# 411V2.net
KiCad netlist of a schematic drawn in EAGLE
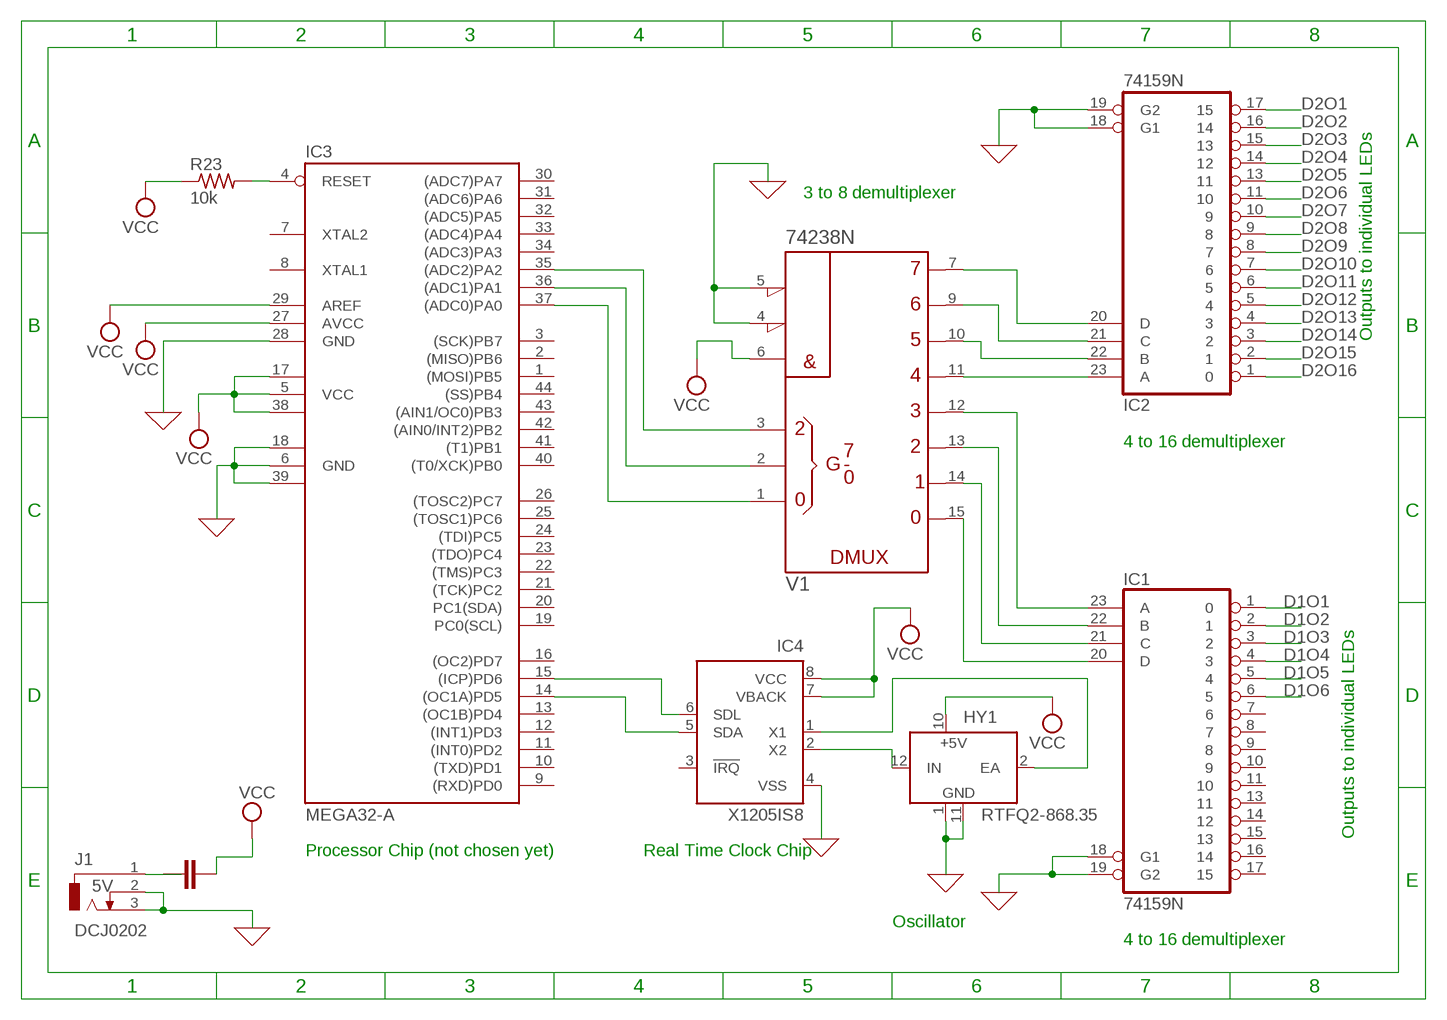
[diagram p0: schematic, sheet 1]
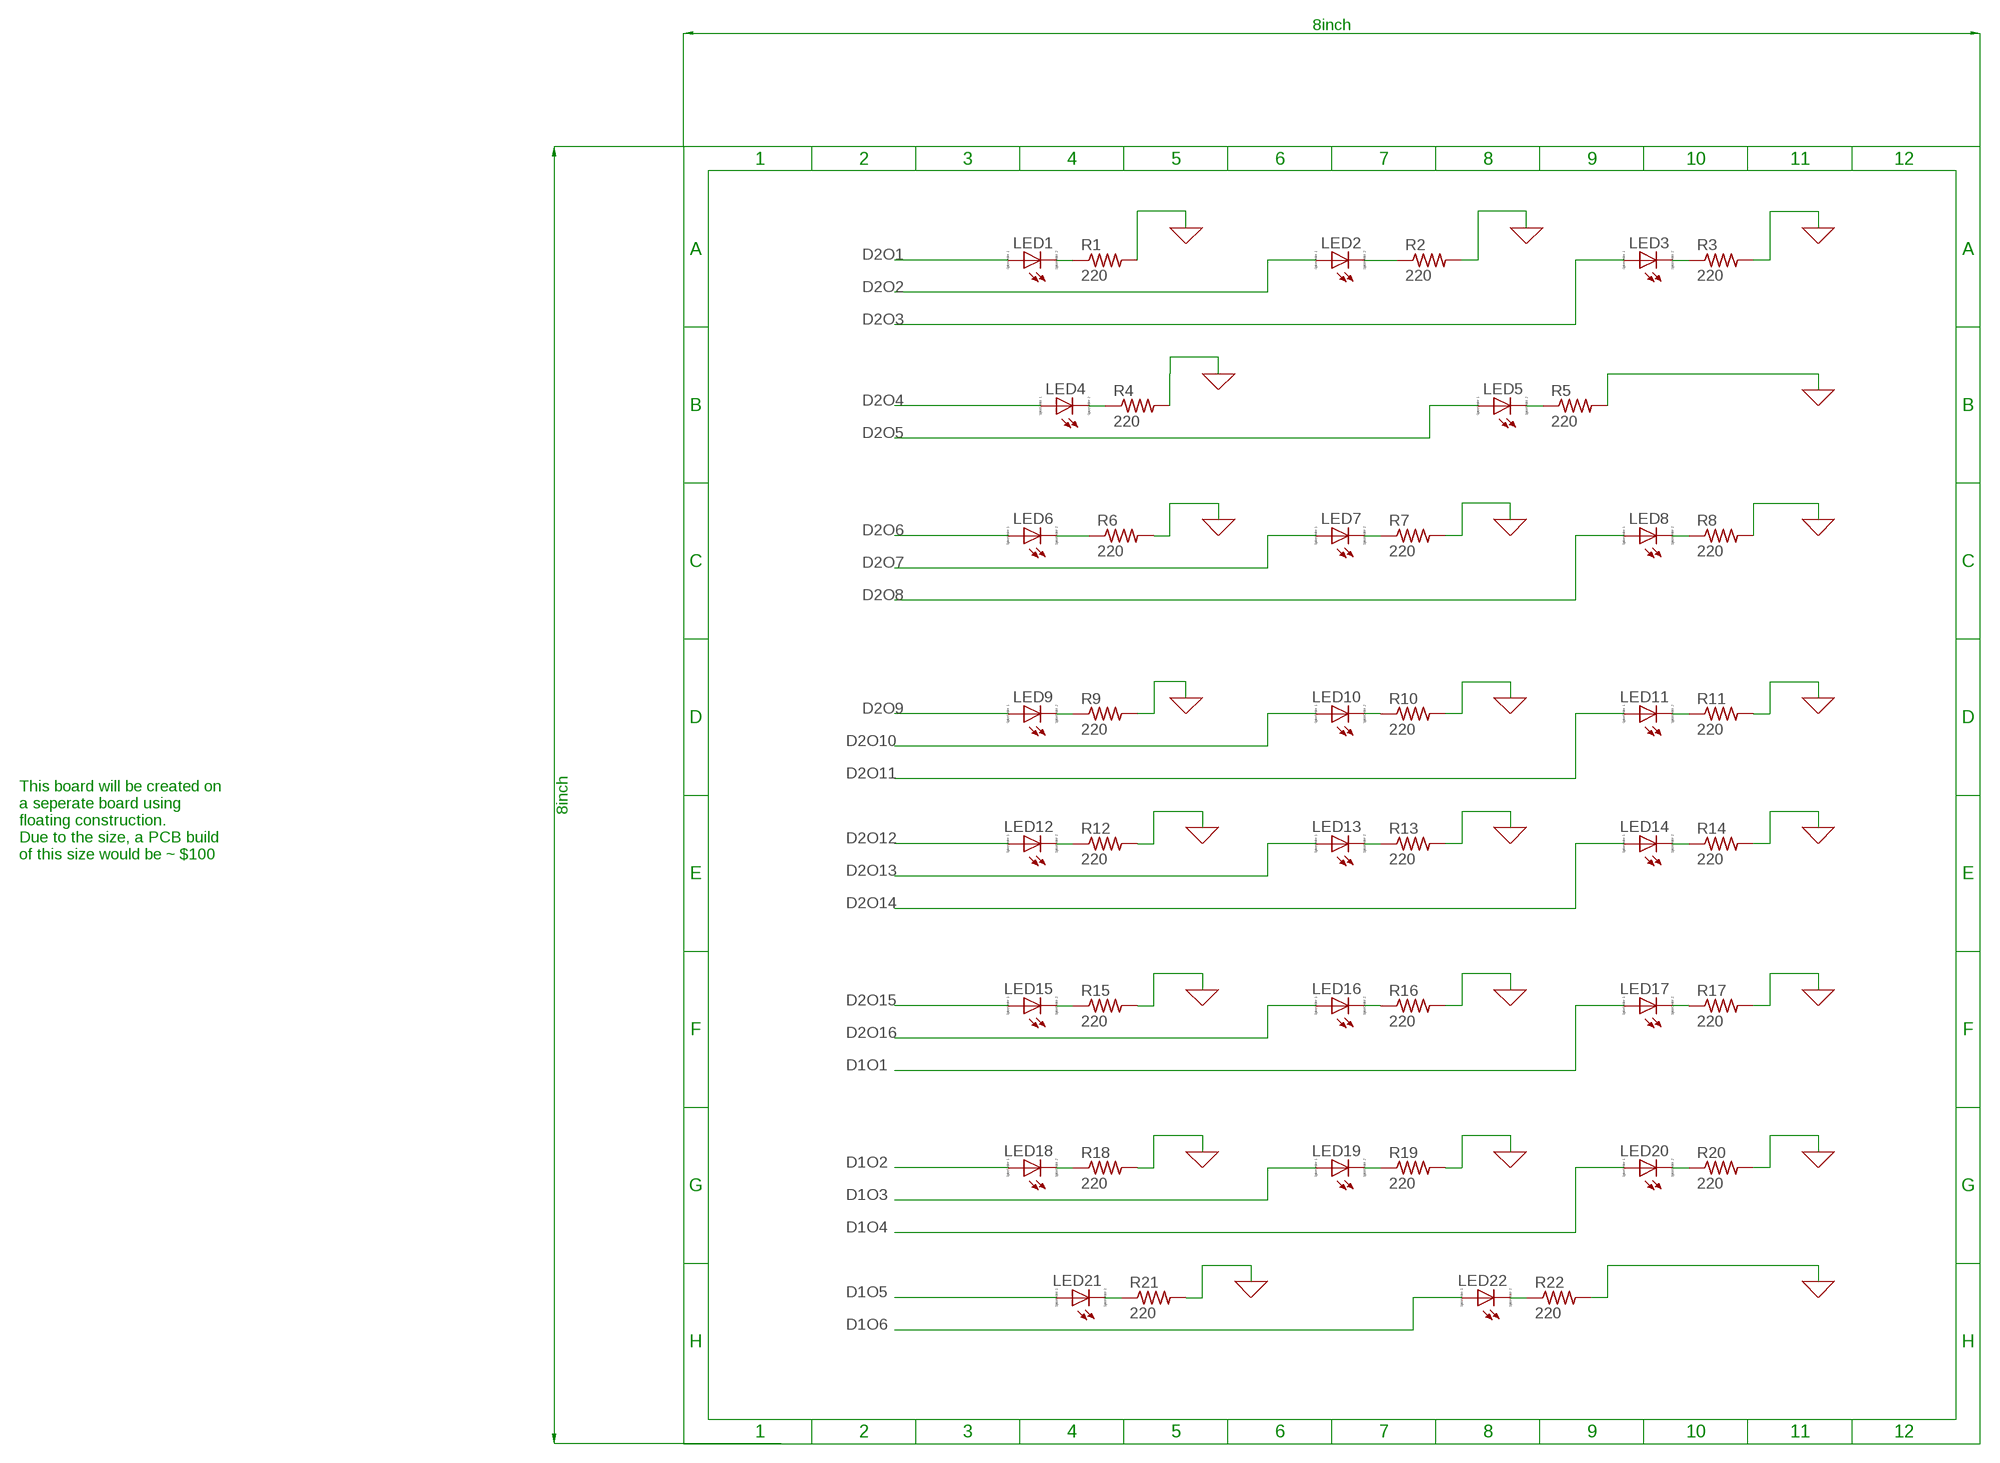
[diagram p1: schematic, sheet 2]

(export (version "E")
  (design (tool "Eeschema 10.0.6"))
  (components
    (comp (ref "LED1")
      (value "LED_ELD260")
      (footprint "eagle-import:LED_LD260")
      (libsource (lib "eagle-import") (part "LED_ELD260"))
    )
    (comp (ref "LED2")
      (value "LED_ELD260")
      (footprint "eagle-import:LED_LD260")
      (libsource (lib "eagle-import") (part "LED_ELD260"))
    )
    (comp (ref "LED3")
      (value "LED_ELD260")
      (footprint "eagle-import:LED_LD260")
      (libsource (lib "eagle-import") (part "LED_ELD260"))
    )
    (comp (ref "LED4")
      (value "LED_ELD260")
      (footprint "eagle-import:LED_LD260")
      (libsource (lib "eagle-import") (part "LED_ELD260"))
    )
    (comp (ref "LED5")
      (value "LED_ELD260")
      (footprint "eagle-import:LED_LD260")
      (libsource (lib "eagle-import") (part "LED_ELD260"))
    )
    (comp (ref "LED6")
      (value "LED_ELD260")
      (footprint "eagle-import:LED_LD260")
      (libsource (lib "eagle-import") (part "LED_ELD260"))
    )
    (comp (ref "LED7")
      (value "LED_ELD260")
      (footprint "eagle-import:LED_LD260")
      (libsource (lib "eagle-import") (part "LED_ELD260"))
    )
    (comp (ref "LED8")
      (value "LED_ELD260")
      (footprint "eagle-import:LED_LD260")
      (libsource (lib "eagle-import") (part "LED_ELD260"))
    )
    (comp (ref "LED9")
      (value "LED_ELD260")
      (footprint "eagle-import:LED_LD260")
      (libsource (lib "eagle-import") (part "LED_ELD260"))
    )
    (comp (ref "LED10")
      (value "LED_ELD260")
      (footprint "eagle-import:LED_LD260")
      (libsource (lib "eagle-import") (part "LED_ELD260"))
    )
    (comp (ref "LED11")
      (value "LED_ELD260")
      (footprint "eagle-import:LED_LD260")
      (libsource (lib "eagle-import") (part "LED_ELD260"))
    )
    (comp (ref "LED12")
      (value "LED_ELD260")
      (footprint "eagle-import:LED_LD260")
      (libsource (lib "eagle-import") (part "LED_ELD260"))
    )
    (comp (ref "LED13")
      (value "LED_ELD260")
      (footprint "eagle-import:LED_LD260")
      (libsource (lib "eagle-import") (part "LED_ELD260"))
    )
    (comp (ref "LED14")
      (value "LED_ELD260")
      (footprint "eagle-import:LED_LD260")
      (libsource (lib "eagle-import") (part "LED_ELD260"))
    )
    (comp (ref "LED15")
      (value "LED_ELD260")
      (footprint "eagle-import:LED_LD260")
      (libsource (lib "eagle-import") (part "LED_ELD260"))
    )
    (comp (ref "LED16")
      (value "LED_ELD260")
      (footprint "eagle-import:LED_LD260")
      (libsource (lib "eagle-import") (part "LED_ELD260"))
    )
    (comp (ref "LED17")
      (value "LED_ELD260")
      (footprint "eagle-import:LED_LD260")
      (libsource (lib "eagle-import") (part "LED_ELD260"))
    )
    (comp (ref "LED18")
      (value "LED_ELD260")
      (footprint "eagle-import:LED_LD260")
      (libsource (lib "eagle-import") (part "LED_ELD260"))
    )
    (comp (ref "LED19")
      (value "LED_ELD260")
      (footprint "eagle-import:LED_LD260")
      (libsource (lib "eagle-import") (part "LED_ELD260"))
    )
    (comp (ref "LED20")
      (value "LED_ELD260")
      (footprint "eagle-import:LED_LD260")
      (libsource (lib "eagle-import") (part "LED_ELD260"))
    )
    (comp (ref "LED21")
      (value "LED_ELD260")
      (footprint "eagle-import:LED_LD260")
      (libsource (lib "eagle-import") (part "LED_ELD260"))
    )
    (comp (ref "LED22")
      (value "LED_ELD260")
      (footprint "eagle-import:LED_LD260")
      (libsource (lib "eagle-import") (part "LED_ELD260"))
    )
    (comp (ref "R1")
      (value "220")
      (footprint "eagle-import:0204_5")
      (libsource (lib "eagle-import") (part "R-US_0204/5"))
    )
    (comp (ref "R2")
      (value "220")
      (footprint "eagle-import:0204_5")
      (libsource (lib "eagle-import") (part "R-US_0204/5"))
    )
    (comp (ref "R3")
      (value "220")
      (footprint "eagle-import:0204_5")
      (libsource (lib "eagle-import") (part "R-US_0204/5"))
    )
    (comp (ref "R4")
      (value "220")
      (footprint "eagle-import:0204_5")
      (libsource (lib "eagle-import") (part "R-US_0204/5"))
    )
    (comp (ref "R5")
      (value "220")
      (footprint "eagle-import:0204_5")
      (libsource (lib "eagle-import") (part "R-US_0204/5"))
    )
    (comp (ref "R6")
      (value "220")
      (footprint "eagle-import:0204_5")
      (libsource (lib "eagle-import") (part "R-US_0204/5"))
    )
    (comp (ref "R7")
      (value "220")
      (footprint "eagle-import:0204_5")
      (libsource (lib "eagle-import") (part "R-US_0204/5"))
    )
    (comp (ref "R8")
      (value "220")
      (footprint "eagle-import:0204_5")
      (libsource (lib "eagle-import") (part "R-US_0204/5"))
    )
    (comp (ref "R9")
      (value "220")
      (footprint "eagle-import:0204_5")
      (libsource (lib "eagle-import") (part "R-US_0204/5"))
    )
    (comp (ref "R10")
      (value "220")
      (footprint "eagle-import:0204_5")
      (libsource (lib "eagle-import") (part "R-US_0204/5"))
    )
    (comp (ref "R11")
      (value "220")
      (footprint "eagle-import:0204_5")
      (libsource (lib "eagle-import") (part "R-US_0204/5"))
    )
    (comp (ref "R12")
      (value "220")
      (footprint "eagle-import:0204_5")
      (libsource (lib "eagle-import") (part "R-US_0204/5"))
    )
    (comp (ref "R13")
      (value "220")
      (footprint "eagle-import:0204_5")
      (libsource (lib "eagle-import") (part "R-US_0204/5"))
    )
    (comp (ref "R14")
      (value "220")
      (footprint "eagle-import:0204_5")
      (libsource (lib "eagle-import") (part "R-US_0204/5"))
    )
    (comp (ref "R15")
      (value "220")
      (footprint "eagle-import:0204_5")
      (libsource (lib "eagle-import") (part "R-US_0204/5"))
    )
    (comp (ref "R16")
      (value "220")
      (footprint "eagle-import:0204_5")
      (libsource (lib "eagle-import") (part "R-US_0204/5"))
    )
    (comp (ref "R17")
      (value "220")
      (footprint "eagle-import:0204_5")
      (libsource (lib "eagle-import") (part "R-US_0204/5"))
    )
    (comp (ref "R18")
      (value "220")
      (footprint "eagle-import:0204_5")
      (libsource (lib "eagle-import") (part "R-US_0204/5"))
    )
    (comp (ref "R19")
      (value "220")
      (footprint "eagle-import:0204_5")
      (libsource (lib "eagle-import") (part "R-US_0204/5"))
    )
    (comp (ref "R20")
      (value "220")
      (footprint "eagle-import:0204_5")
      (libsource (lib "eagle-import") (part "R-US_0204/5"))
    )
    (comp (ref "R21")
      (value "220")
      (footprint "eagle-import:0204_5")
      (libsource (lib "eagle-import") (part "R-US_0204/5"))
    )
    (comp (ref "R22")
      (value "220")
      (footprint "eagle-import:0204_5")
      (libsource (lib "eagle-import") (part "R-US_0204/5"))
    )
    (comp (ref "HY1")
      (value "RTFQ2-868.35")
      (footprint "eagle-import:RTFQ2")
      (libsource (lib "eagle-import") (part "RTFQ2-868.35"))
    )
    (comp (ref "IC1")
      (value "74159N")
      (footprint "eagle-import:DIL24-6")
      (libsource (lib "eagle-import") (part "74159N"))
    )
    (comp (ref "IC2")
      (value "74159N")
      (footprint "eagle-import:DIL24-6")
      (libsource (lib "eagle-import") (part "74159N"))
    )
    (comp (ref "IC3")
      (value "MEGA32-A")
      (footprint "eagle-import:TQFP44")
      (fields (field (name "MPN") "ATMEGA32-16AU"))
      (libsource (lib "eagle-import") (part "MEGA32-A"))
    )
    (comp (ref "IC4")
      (value "X1205IS8")
      (footprint "eagle-import:SO-08")
      (libsource (lib "eagle-import") (part "X1205S8I"))
    )
    (comp (ref "J1")
      (value "DCJ0202")
      (footprint "eagle-import:DCJ0202")
      (fields (field (name "OC_FARNELL") "unknown") (field (name "OC_FARNELL_1") "5V"))
      (libsource (lib "eagle-import") (part "DCJ0202"))
    )
    (comp (ref "R23")
      (value "10k")
      (footprint "eagle-import:0204V")
      (libsource (lib "eagle-import") (part "resistor_348_R-US_0204/2V"))
    )
    (comp (ref "V1")
      (value "74238N")
      (footprint "eagle-import:DIL16")
      (libsource (lib "eagle-import") (part "74238N"))
    )
  )
  (nets
    (net (code "1") (name "0") (class "Default")
      (node (ref "HY1") (pin "1") (pinfunction "GND_1") (pintype "power_in"))
      (node (ref "HY1") (pin "11") (pinfunction "GND_11") (pintype "power_in"))
      (node (ref "IC1") (pin "18") (pinfunction "G1_18") (pintype "input"))
      (node (ref "IC1") (pin "19") (pinfunction "G2_19") (pintype "input"))
      (node (ref "IC2") (pin "18") (pinfunction "G1_18") (pintype "input"))
      (node (ref "IC2") (pin "19") (pinfunction "G2_19") (pintype "input"))
      (node (ref "IC3") (pin "18") (pinfunction "GND1_18") (pintype "power_in"))
      (node (ref "IC3") (pin "28") (pinfunction "GND_28") (pintype "power_in"))
      (node (ref "IC3") (pin "39") (pinfunction "GND2_39") (pintype "power_in"))
      (node (ref "IC3") (pin "6") (pinfunction "GND_6") (pintype "power_in"))
      (node (ref "IC4") (pin "4") (pinfunction "VSS_4") (pintype "power_in"))
      (node (ref "J1") (pin "2") (pinfunction "2_2") (pintype "passive"))
      (node (ref "J1") (pin "3") (pinfunction "3_3") (pintype "passive"))
      (node (ref "R1") (pin "2") (pinfunction "2_2") (pintype "passive"))
      (node (ref "R10") (pin "2") (pinfunction "2_2") (pintype "passive"))
      (node (ref "R11") (pin "2") (pinfunction "2_2") (pintype "passive"))
      (node (ref "R12") (pin "2") (pinfunction "2_2") (pintype "passive"))
      (node (ref "R13") (pin "2") (pinfunction "2_2") (pintype "passive"))
      (node (ref "R14") (pin "2") (pinfunction "2_2") (pintype "passive"))
      (node (ref "R15") (pin "2") (pinfunction "2_2") (pintype "passive"))
      (node (ref "R16") (pin "2") (pinfunction "2_2") (pintype "passive"))
      (node (ref "R17") (pin "2") (pinfunction "2_2") (pintype "passive"))
      (node (ref "R18") (pin "2") (pinfunction "2_2") (pintype "passive"))
      (node (ref "R19") (pin "2") (pinfunction "2_2") (pintype "passive"))
      (node (ref "R2") (pin "2") (pinfunction "2_2") (pintype "passive"))
      (node (ref "R20") (pin "2") (pinfunction "2_2") (pintype "passive"))
      (node (ref "R21") (pin "2") (pinfunction "2_2") (pintype "passive"))
      (node (ref "R22") (pin "2") (pinfunction "2_2") (pintype "passive"))
      (node (ref "R3") (pin "2") (pinfunction "2_2") (pintype "passive"))
      (node (ref "R4") (pin "2") (pinfunction "2_2") (pintype "passive"))
      (node (ref "R5") (pin "2") (pinfunction "2_2") (pintype "passive"))
      (node (ref "R6") (pin "2") (pinfunction "2_2") (pintype "passive"))
      (node (ref "R7") (pin "2") (pinfunction "2_2") (pintype "passive"))
      (node (ref "R8") (pin "2") (pinfunction "2_2") (pintype "passive"))
      (node (ref "R9") (pin "2") (pinfunction "2_2") (pintype "passive"))
      (node (ref "V1") (pin "4") (pinfunction "~{G2A}_4") (pintype "input"))
      (node (ref "V1") (pin "5") (pinfunction "~{G2B}_5") (pintype "input"))
    )
    (net (code "2") (name "D1O1") (class "Default")
      (node (ref "IC1") (pin "1") (pinfunction "0_1") (pintype "open_collector"))
      (node (ref "LED17") (pin "A") (pinfunction "A_A") (pintype "passive"))
    )
    (net (code "3") (name "D1O2") (class "Default")
      (node (ref "IC1") (pin "2") (pinfunction "1_2") (pintype "open_collector"))
      (node (ref "LED18") (pin "A") (pinfunction "A_A") (pintype "passive"))
    )
    (net (code "4") (name "D1O3") (class "Default")
      (node (ref "IC1") (pin "3") (pinfunction "2_3") (pintype "open_collector"))
      (node (ref "LED19") (pin "A") (pinfunction "A_A") (pintype "passive"))
    )
    (net (code "5") (name "D1O4") (class "Default")
      (node (ref "IC1") (pin "4") (pinfunction "3_4") (pintype "open_collector"))
      (node (ref "LED20") (pin "A") (pinfunction "A_A") (pintype "passive"))
    )
    (net (code "6") (name "D1O5") (class "Default")
      (node (ref "IC1") (pin "5") (pinfunction "4_5") (pintype "open_collector"))
      (node (ref "LED21") (pin "A") (pinfunction "A_A") (pintype "passive"))
    )
    (net (code "7") (name "D1O6") (class "Default")
      (node (ref "IC1") (pin "6") (pinfunction "5_6") (pintype "open_collector"))
      (node (ref "LED22") (pin "A") (pinfunction "A_A") (pintype "passive"))
    )
    (net (code "8") (name "D2O1") (class "Default")
      (node (ref "IC2") (pin "17") (pinfunction "15_17") (pintype "open_collector"))
      (node (ref "LED1") (pin "A") (pinfunction "A_A") (pintype "passive"))
    )
    (net (code "9") (name "D2O2") (class "Default")
      (node (ref "IC2") (pin "16") (pinfunction "14_16") (pintype "open_collector"))
      (node (ref "LED2") (pin "A") (pinfunction "A_A") (pintype "passive"))
    )
    (net (code "10") (name "D2O3") (class "Default")
      (node (ref "IC2") (pin "15") (pinfunction "13_15") (pintype "open_collector"))
      (node (ref "LED3") (pin "A") (pinfunction "A_A") (pintype "passive"))
    )
    (net (code "11") (name "D2O4") (class "Default")
      (node (ref "IC2") (pin "14") (pinfunction "12_14") (pintype "open_collector"))
      (node (ref "LED4") (pin "A") (pinfunction "A_A") (pintype "passive"))
    )
    (net (code "12") (name "D2O5") (class "Default")
      (node (ref "IC2") (pin "13") (pinfunction "11_13") (pintype "open_collector"))
      (node (ref "LED5") (pin "A") (pinfunction "A_A") (pintype "passive"))
    )
    (net (code "13") (name "D2O6") (class "Default")
      (node (ref "IC2") (pin "11") (pinfunction "10_11") (pintype "open_collector"))
      (node (ref "LED6") (pin "A") (pinfunction "A_A") (pintype "passive"))
    )
    (net (code "14") (name "D2O7") (class "Default")
      (node (ref "IC2") (pin "10") (pinfunction "9_10") (pintype "open_collector"))
      (node (ref "LED7") (pin "A") (pinfunction "A_A") (pintype "passive"))
    )
    (net (code "15") (name "D2O8") (class "Default")
      (node (ref "IC2") (pin "9") (pinfunction "8_9") (pintype "open_collector"))
      (node (ref "LED8") (pin "A") (pinfunction "A_A") (pintype "passive"))
    )
    (net (code "16") (name "D2O9") (class "Default")
      (node (ref "IC2") (pin "8") (pinfunction "7_8") (pintype "open_collector"))
      (node (ref "LED9") (pin "A") (pinfunction "A_A") (pintype "passive"))
    )
    (net (code "17") (name "D2O10") (class "Default")
      (node (ref "IC2") (pin "7") (pinfunction "6_7") (pintype "open_collector"))
      (node (ref "LED10") (pin "A") (pinfunction "A_A") (pintype "passive"))
    )
    (net (code "18") (name "D2O11") (class "Default")
      (node (ref "IC2") (pin "6") (pinfunction "5_6") (pintype "open_collector"))
      (node (ref "LED11") (pin "A") (pinfunction "A_A") (pintype "passive"))
    )
    (net (code "19") (name "D2O12") (class "Default")
      (node (ref "IC2") (pin "5") (pinfunction "4_5") (pintype "open_collector"))
      (node (ref "LED12") (pin "A") (pinfunction "A_A") (pintype "passive"))
    )
    (net (code "20") (name "D2O13") (class "Default")
      (node (ref "IC2") (pin "4") (pinfunction "3_4") (pintype "open_collector"))
      (node (ref "LED13") (pin "A") (pinfunction "A_A") (pintype "passive"))
    )
    (net (code "21") (name "D2O14") (class "Default")
      (node (ref "IC2") (pin "3") (pinfunction "2_3") (pintype "open_collector"))
      (node (ref "LED14") (pin "A") (pinfunction "A_A") (pintype "passive"))
    )
    (net (code "22") (name "D2O15") (class "Default")
      (node (ref "IC2") (pin "2") (pinfunction "1_2") (pintype "open_collector"))
      (node (ref "LED15") (pin "A") (pinfunction "A_A") (pintype "passive"))
    )
    (net (code "23") (name "D2O16") (class "Default")
      (node (ref "IC2") (pin "1") (pinfunction "0_1") (pintype "open_collector"))
      (node (ref "LED16") (pin "A") (pinfunction "A_A") (pintype "passive"))
    )
    (net (code "24") (name "Net-(HY1-EA)") (class "Default")
      (node (ref "HY1") (pin "2") (pinfunction "EA_2") (pintype "output"))
      (node (ref "IC4") (pin "1") (pinfunction "X1_1") (pintype "input"))
    )
    (net (code "25") (name "Net-(HY1-IN)") (class "Default")
      (node (ref "HY1") (pin "12") (pinfunction "IN_12") (pintype "input"))
      (node (ref "IC4") (pin "2") (pinfunction "X2_2") (pintype "output"))
    )
    (net (code "26") (name "Net-(IC1A-A)") (class "Default")
      (node (ref "IC1") (pin "23") (pinfunction "A_23") (pintype "input"))
      (node (ref "V1") (pin "12") (pinfunction "Y3_12") (pintype "output"))
    )
    (net (code "27") (name "Net-(IC1A-B)") (class "Default")
      (node (ref "IC1") (pin "22") (pinfunction "B_22") (pintype "input"))
      (node (ref "V1") (pin "13") (pinfunction "Y2_13") (pintype "output"))
    )
    (net (code "28") (name "Net-(IC1A-C)") (class "Default")
      (node (ref "IC1") (pin "21") (pinfunction "C_21") (pintype "input"))
      (node (ref "V1") (pin "14") (pinfunction "Y1_14") (pintype "output"))
    )
    (net (code "29") (name "Net-(IC1A-D)") (class "Default")
      (node (ref "IC1") (pin "20") (pinfunction "D_20") (pintype "input"))
      (node (ref "V1") (pin "15") (pinfunction "Y0_15") (pintype "output"))
    )
    (net (code "30") (name "Net-(IC2A-A)") (class "Default")
      (node (ref "IC2") (pin "23") (pinfunction "A_23") (pintype "input"))
      (node (ref "V1") (pin "11") (pinfunction "Y4_11") (pintype "output"))
    )
    (net (code "31") (name "Net-(IC2A-B)") (class "Default")
      (node (ref "IC2") (pin "22") (pinfunction "B_22") (pintype "input"))
      (node (ref "V1") (pin "10") (pinfunction "Y5_10") (pintype "output"))
    )
    (net (code "32") (name "Net-(IC2A-C)") (class "Default")
      (node (ref "IC2") (pin "21") (pinfunction "C_21") (pintype "input"))
      (node (ref "V1") (pin "9") (pinfunction "Y6_9") (pintype "output"))
    )
    (net (code "33") (name "Net-(IC2A-D)") (class "Default")
      (node (ref "IC2") (pin "20") (pinfunction "D_20") (pintype "input"))
      (node (ref "V1") (pin "7") (pinfunction "Y7_7") (pintype "output"))
    )
    (net (code "34") (name "Net-(IC3-(ADC0)PA0)") (class "Default")
      (node (ref "IC3") (pin "37") (pinfunction "(ADC0)PA0_37") (pintype "bidirectional"))
      (node (ref "V1") (pin "1") (pinfunction "A_1") (pintype "input"))
    )
    (net (code "35") (name "Net-(IC3-(ADC1)PA1)") (class "Default")
      (node (ref "IC3") (pin "36") (pinfunction "(ADC1)PA1_36") (pintype "bidirectional"))
      (node (ref "V1") (pin "2") (pinfunction "B_2") (pintype "input"))
    )
    (net (code "36") (name "Net-(IC3-(ADC2)PA2)") (class "Default")
      (node (ref "IC3") (pin "35") (pinfunction "(ADC2)PA2_35") (pintype "bidirectional"))
      (node (ref "V1") (pin "3") (pinfunction "C_3") (pintype "input"))
    )
    (net (code "37") (name "Net-(IC3-(ICP)PD6)") (class "Default")
      (node (ref "IC3") (pin "15") (pinfunction "(ICP)PD6_15") (pintype "bidirectional"))
      (node (ref "IC4") (pin "6") (pinfunction "SDL_6") (pintype "input"))
    )
    (net (code "38") (name "Net-(IC3-(OC1A)PD5)") (class "Default")
      (node (ref "IC3") (pin "14") (pinfunction "(OC1A)PD5_14") (pintype "bidirectional"))
      (node (ref "IC4") (pin "5") (pinfunction "SDA_5") (pintype "bidirectional"))
    )
    (net (code "39") (name "Net-(IC3-RESET)") (class "Default")
      (node (ref "IC3") (pin "4") (pinfunction "RESET_4") (pintype "input"))
      (node (ref "R23") (pin "2") (pinfunction "2_2") (pintype "passive"))
    )
    (net (code "40") (name "Net-(LED1-C)") (class "Default")
      (node (ref "LED1") (pin "K") (pinfunction "C_K") (pintype "passive"))
      (node (ref "R1") (pin "1") (pinfunction "1_1") (pintype "passive"))
    )
    (net (code "41") (name "Net-(LED2-C)") (class "Default")
      (node (ref "LED2") (pin "K") (pinfunction "C_K") (pintype "passive"))
      (node (ref "R2") (pin "1") (pinfunction "1_1") (pintype "passive"))
    )
    (net (code "42") (name "Net-(LED3-C)") (class "Default")
      (node (ref "LED3") (pin "K") (pinfunction "C_K") (pintype "passive"))
      (node (ref "R3") (pin "1") (pinfunction "1_1") (pintype "passive"))
    )
    (net (code "43") (name "Net-(LED4-C)") (class "Default")
      (node (ref "LED4") (pin "K") (pinfunction "C_K") (pintype "passive"))
      (node (ref "R4") (pin "1") (pinfunction "1_1") (pintype "passive"))
    )
    (net (code "44") (name "Net-(LED5-C)") (class "Default")
      (node (ref "LED5") (pin "K") (pinfunction "C_K") (pintype "passive"))
      (node (ref "R5") (pin "1") (pinfunction "1_1") (pintype "passive"))
    )
    (net (code "45") (name "Net-(LED6-C)") (class "Default")
      (node (ref "LED6") (pin "K") (pinfunction "C_K") (pintype "passive"))
      (node (ref "R6") (pin "1") (pinfunction "1_1") (pintype "passive"))
    )
    (net (code "46") (name "Net-(LED7-C)") (class "Default")
      (node (ref "LED7") (pin "K") (pinfunction "C_K") (pintype "passive"))
      (node (ref "R7") (pin "1") (pinfunction "1_1") (pintype "passive"))
    )
    (net (code "47") (name "Net-(LED8-C)") (class "Default")
      (node (ref "LED8") (pin "K") (pinfunction "C_K") (pintype "passive"))
      (node (ref "R8") (pin "1") (pinfunction "1_1") (pintype "passive"))
    )
    (net (code "48") (name "Net-(LED9-C)") (class "Default")
      (node (ref "LED9") (pin "K") (pinfunction "C_K") (pintype "passive"))
      (node (ref "R9") (pin "1") (pinfunction "1_1") (pintype "passive"))
    )
    (net (code "49") (name "Net-(LED10-C)") (class "Default")
      (node (ref "LED10") (pin "K") (pinfunction "C_K") (pintype "passive"))
      (node (ref "R10") (pin "1") (pinfunction "1_1") (pintype "passive"))
    )
    (net (code "50") (name "Net-(LED11-C)") (class "Default")
      (node (ref "LED11") (pin "K") (pinfunction "C_K") (pintype "passive"))
      (node (ref "R11") (pin "1") (pinfunction "1_1") (pintype "passive"))
    )
    (net (code "51") (name "Net-(LED12-C)") (class "Default")
      (node (ref "LED12") (pin "K") (pinfunction "C_K") (pintype "passive"))
      (node (ref "R12") (pin "1") (pinfunction "1_1") (pintype "passive"))
    )
    (net (code "52") (name "Net-(LED13-C)") (class "Default")
      (node (ref "LED13") (pin "K") (pinfunction "C_K") (pintype "passive"))
      (node (ref "R13") (pin "1") (pinfunction "1_1") (pintype "passive"))
    )
    (net (code "53") (name "Net-(LED14-C)") (class "Default")
      (node (ref "LED14") (pin "K") (pinfunction "C_K") (pintype "passive"))
      (node (ref "R14") (pin "1") (pinfunction "1_1") (pintype "passive"))
    )
    (net (code "54") (name "Net-(LED15-C)") (class "Default")
      (node (ref "LED15") (pin "K") (pinfunction "C_K") (pintype "passive"))
      (node (ref "R15") (pin "1") (pinfunction "1_1") (pintype "passive"))
    )
    (net (code "55") (name "Net-(LED16-C)") (class "Default")
      (node (ref "LED16") (pin "K") (pinfunction "C_K") (pintype "passive"))
      (node (ref "R16") (pin "1") (pinfunction "1_1") (pintype "passive"))
    )
    (net (code "56") (name "Net-(LED17-C)") (class "Default")
      (node (ref "LED17") (pin "K") (pinfunction "C_K") (pintype "passive"))
      (node (ref "R17") (pin "1") (pinfunction "1_1") (pintype "passive"))
    )
    (net (code "57") (name "Net-(LED18-C)") (class "Default")
      (node (ref "LED18") (pin "K") (pinfunction "C_K") (pintype "passive"))
      (node (ref "R18") (pin "1") (pinfunction "1_1") (pintype "passive"))
    )
    (net (code "58") (name "Net-(LED19-C)") (class "Default")
      (node (ref "LED19") (pin "K") (pinfunction "C_K") (pintype "passive"))
      (node (ref "R19") (pin "1") (pinfunction "1_1") (pintype "passive"))
    )
    (net (code "59") (name "Net-(LED20-C)") (class "Default")
      (node (ref "LED20") (pin "K") (pinfunction "C_K") (pintype "passive"))
      (node (ref "R20") (pin "1") (pinfunction "1_1") (pintype "passive"))
    )
    (net (code "60") (name "Net-(LED21-C)") (class "Default")
      (node (ref "LED21") (pin "K") (pinfunction "C_K") (pintype "passive"))
      (node (ref "R21") (pin "1") (pinfunction "1_1") (pintype "passive"))
    )
    (net (code "61") (name "Net-(LED22-C)") (class "Default")
      (node (ref "LED22") (pin "K") (pinfunction "C_K") (pintype "passive"))
      (node (ref "R22") (pin "1") (pinfunction "1_1") (pintype "passive"))
    )
    (net (code "62") (name "VCC") (class "Default")
      (node (ref "HY1") (pin "10") (pinfunction "+5V_10") (pintype "power_in"))
      (node (ref "IC3") (pin "17") (pinfunction "VCC1_17") (pintype "power_in"))
      (node (ref "IC3") (pin "27") (pinfunction "AVCC_27") (pintype "power_in"))
      (node (ref "IC3") (pin "29") (pinfunction "AREF_29") (pintype "passive"))
      (node (ref "IC3") (pin "38") (pinfunction "VCC2_38") (pintype "power_in"))
      (node (ref "IC3") (pin "5") (pinfunction "VCC_5") (pintype "power_in"))
      (node (ref "IC4") (pin "7") (pinfunction "VBACK_7") (pintype "input"))
      (node (ref "IC4") (pin "8") (pinfunction "VCC_8") (pintype "power_in"))
      (node (ref "R23") (pin "1") (pinfunction "1_1") (pintype "passive"))
      (node (ref "V1") (pin "6") (pinfunction "G1_6") (pintype "input"))
    )
    (net (code "63") (name "unconnected-(IC1A-6-Pad7)") (class "Default")
      (node (ref "IC1") (pin "7") (pinfunction "6_7") (pintype "open_collector"))
    )
    (net (code "64") (name "unconnected-(IC1A-7-Pad8)") (class "Default")
      (node (ref "IC1") (pin "8") (pinfunction "7_8") (pintype "open_collector"))
    )
    (net (code "65") (name "unconnected-(IC1A-8-Pad9)") (class "Default")
      (node (ref "IC1") (pin "9") (pinfunction "8_9") (pintype "open_collector"))
    )
    (net (code "66") (name "unconnected-(IC1A-9-Pad10)") (class "Default")
      (node (ref "IC1") (pin "10") (pinfunction "9_10") (pintype "open_collector"))
    )
    (net (code "67") (name "unconnected-(IC1A-10-Pad11)") (class "Default")
      (node (ref "IC1") (pin "11") (pinfunction "10_11") (pintype "open_collector"))
    )
    (net (code "68") (name "unconnected-(IC1A-11-Pad13)") (class "Default")
      (node (ref "IC1") (pin "13") (pinfunction "11_13") (pintype "open_collector"))
    )
    (net (code "69") (name "unconnected-(IC1A-12-Pad14)") (class "Default")
      (node (ref "IC1") (pin "14") (pinfunction "12_14") (pintype "open_collector"))
    )
    (net (code "70") (name "unconnected-(IC1A-13-Pad15)") (class "Default")
      (node (ref "IC1") (pin "15") (pinfunction "13_15") (pintype "open_collector"))
    )
    (net (code "71") (name "unconnected-(IC1A-14-Pad16)") (class "Default")
      (node (ref "IC1") (pin "16") (pinfunction "14_16") (pintype "open_collector"))
    )
    (net (code "72") (name "unconnected-(IC1A-15-Pad17)") (class "Default")
      (node (ref "IC1") (pin "17") (pinfunction "15_17") (pintype "open_collector"))
    )
    (net (code "73") (name "unconnected-(IC3-(ADC3)PA3-Pad34)") (class "Default")
      (node (ref "IC3") (pin "34") (pinfunction "(ADC3)PA3_34") (pintype "bidirectional"))
    )
    (net (code "74") (name "unconnected-(IC3-(ADC4)PA4-Pad33)") (class "Default")
      (node (ref "IC3") (pin "33") (pinfunction "(ADC4)PA4_33") (pintype "bidirectional"))
    )
    (net (code "75") (name "unconnected-(IC3-(ADC5)PA5-Pad32)") (class "Default")
      (node (ref "IC3") (pin "32") (pinfunction "(ADC5)PA5_32") (pintype "bidirectional"))
    )
    (net (code "76") (name "unconnected-(IC3-(ADC6)PA6-Pad31)") (class "Default")
      (node (ref "IC3") (pin "31") (pinfunction "(ADC6)PA6_31") (pintype "bidirectional"))
    )
    (net (code "77") (name "unconnected-(IC3-(ADC7)PA7-Pad30)") (class "Default")
      (node (ref "IC3") (pin "30") (pinfunction "(ADC7)PA7_30") (pintype "bidirectional"))
    )
    (net (code "78") (name "unconnected-(IC3-(AIN0{slash}INT2)PB2-Pad42)") (class "Default")
      (node (ref "IC3") (pin "42") (pinfunction "(AIN0/INT2)PB2_42") (pintype "bidirectional"))
    )
    (net (code "79") (name "unconnected-(IC3-(AIN1{slash}OC0)PB3-Pad43)") (class "Default")
      (node (ref "IC3") (pin "43") (pinfunction "(AIN1/OC0)PB3_43") (pintype "bidirectional"))
    )
    (net (code "80") (name "unconnected-(IC3-(INT0)PD2-Pad11)") (class "Default")
      (node (ref "IC3") (pin "11") (pinfunction "(INT0)PD2_11") (pintype "bidirectional"))
    )
    (net (code "81") (name "unconnected-(IC3-(INT1)PD3-Pad12)") (class "Default")
      (node (ref "IC3") (pin "12") (pinfunction "(INT1)PD3_12") (pintype "bidirectional"))
    )
    (net (code "82") (name "unconnected-(IC3-(MISO)PB6-Pad2)") (class "Default")
      (node (ref "IC3") (pin "2") (pinfunction "(MISO)PB6_2") (pintype "bidirectional"))
    )
    (net (code "83") (name "unconnected-(IC3-(MOSI)PB5-Pad1)") (class "Default")
      (node (ref "IC3") (pin "1") (pinfunction "(MOSI)PB5_1") (pintype "bidirectional"))
    )
    (net (code "84") (name "unconnected-(IC3-(OC1B)PD4-Pad13)") (class "Default")
      (node (ref "IC3") (pin "13") (pinfunction "(OC1B)PD4_13") (pintype "bidirectional"))
    )
    (net (code "85") (name "unconnected-(IC3-(OC2)PD7-Pad16)") (class "Default")
      (node (ref "IC3") (pin "16") (pinfunction "(OC2)PD7_16") (pintype "bidirectional"))
    )
    (net (code "86") (name "unconnected-(IC3-(RXD)PD0-Pad9)") (class "Default")
      (node (ref "IC3") (pin "9") (pinfunction "(RXD)PD0_9") (pintype "bidirectional"))
    )
    (net (code "87") (name "unconnected-(IC3-(SCK)PB7-Pad3)") (class "Default")
      (node (ref "IC3") (pin "3") (pinfunction "(SCK)PB7_3") (pintype "bidirectional"))
    )
    (net (code "88") (name "unconnected-(IC3-(SS)PB4-Pad44)") (class "Default")
      (node (ref "IC3") (pin "44") (pinfunction "(SS)PB4_44") (pintype "bidirectional"))
    )
    (net (code "89") (name "unconnected-(IC3-(T0{slash}XCK)PB0-Pad40)") (class "Default")
      (node (ref "IC3") (pin "40") (pinfunction "(T0/XCK)PB0_40") (pintype "bidirectional"))
    )
    (net (code "90") (name "unconnected-(IC3-(T1)PB1-Pad41)") (class "Default")
      (node (ref "IC3") (pin "41") (pinfunction "(T1)PB1_41") (pintype "bidirectional"))
    )
    (net (code "91") (name "unconnected-(IC3-(TCK)PC2-Pad21)") (class "Default")
      (node (ref "IC3") (pin "21") (pinfunction "(TCK)PC2_21") (pintype "bidirectional"))
    )
    (net (code "92") (name "unconnected-(IC3-(TDI)PC5-Pad24)") (class "Default")
      (node (ref "IC3") (pin "24") (pinfunction "(TDI)PC5_24") (pintype "bidirectional"))
    )
    (net (code "93") (name "unconnected-(IC3-(TDO)PC4-Pad23)") (class "Default")
      (node (ref "IC3") (pin "23") (pinfunction "(TDO)PC4_23") (pintype "bidirectional"))
    )
    (net (code "94") (name "unconnected-(IC3-(TMS)PC3-Pad22)") (class "Default")
      (node (ref "IC3") (pin "22") (pinfunction "(TMS)PC3_22") (pintype "bidirectional"))
    )
    (net (code "95") (name "unconnected-(IC3-(TOSC1)PC6-Pad25)") (class "Default")
      (node (ref "IC3") (pin "25") (pinfunction "(TOSC1)PC6_25") (pintype "bidirectional"))
    )
    (net (code "96") (name "unconnected-(IC3-(TOSC2)PC7-Pad26)") (class "Default")
      (node (ref "IC3") (pin "26") (pinfunction "(TOSC2)PC7_26") (pintype "bidirectional"))
    )
    (net (code "97") (name "unconnected-(IC3-(TXD)PD1-Pad10)") (class "Default")
      (node (ref "IC3") (pin "10") (pinfunction "(TXD)PD1_10") (pintype "bidirectional"))
    )
    (net (code "98") (name "unconnected-(IC3-PC0(SCL)-Pad19)") (class "Default")
      (node (ref "IC3") (pin "19") (pinfunction "PC0(SCL)_19") (pintype "bidirectional"))
    )
    (net (code "99") (name "unconnected-(IC3-PC1(SDA)-Pad20)") (class "Default")
      (node (ref "IC3") (pin "20") (pinfunction "PC1(SDA)_20") (pintype "bidirectional"))
    )
    (net (code "100") (name "unconnected-(IC3-XTAL1-Pad8)") (class "Default")
      (node (ref "IC3") (pin "8") (pinfunction "XTAL1_8") (pintype "bidirectional"))
    )
    (net (code "101") (name "unconnected-(IC3-XTAL2-Pad7)") (class "Default")
      (node (ref "IC3") (pin "7") (pinfunction "XTAL2_7") (pintype "bidirectional"))
    )
    (net (code "102") (name "unconnected-(IC4-~{IRQ}-Pad3)") (class "Default")
      (node (ref "IC4") (pin "3") (pinfunction "~{IRQ}_3") (pintype "output"))
    )
    (net (code "103") (name "unconnected-(J1-Pad1)") (class "Default")
      (node (ref "J1") (pin "1") (pinfunction "1_1") (pintype "passive"))
    )
  )
)
